# Memory.net
KiCad netlist of a schematic drawn in Altium Designer
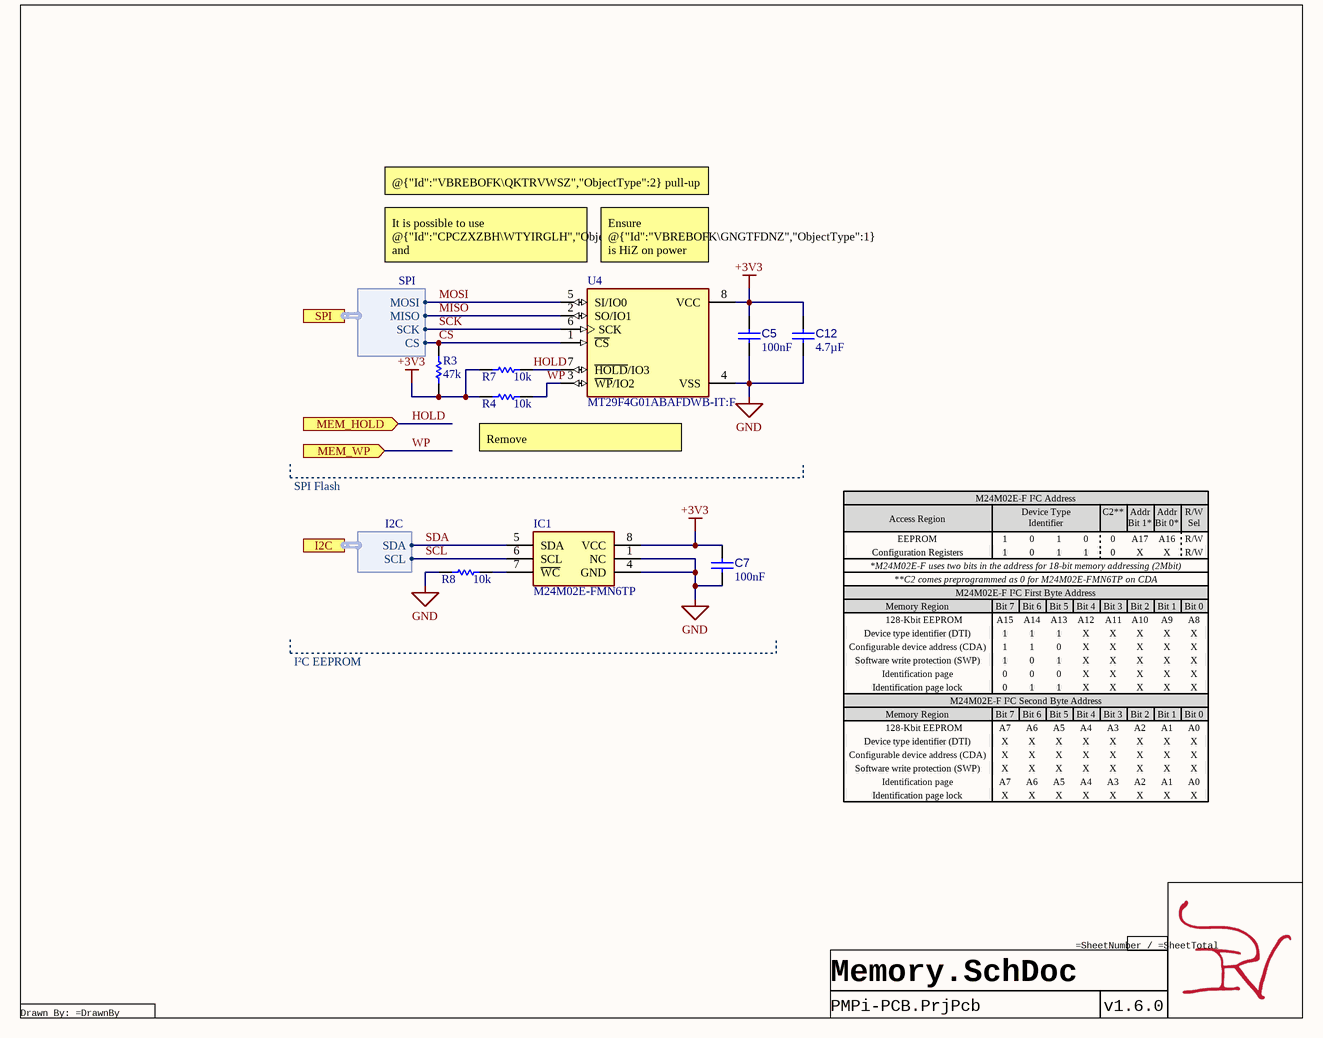
[diagram p0: Memory.SchDoc]

(export (version "E")
  (design (tool "Eeschema 10.0.6"))
  (components
    (comp (ref "C5")
      (value "100nF")
      (footprint "CAP 0402_1005")
      (fields (field (name "TOLERANCE") "10%") (field (name "Comment") "CAP-NP-2"))
      (libsource (lib "IIT Motorsports") (part "CAP-NP-2"))
    )
    (comp (ref "C7")
      (value "100nF")
      (footprint "CAP 0402_1005")
      (fields (field (name "TOLERANCE") "10%") (field (name "Comment") "CAP-NP-2"))
      (libsource (lib "IIT Motorsports") (part "CAP-NP-2"))
    )
    (comp (ref "C12")
      (value "4.7µF")
      (footprint "CAP 0402_1005")
      (fields (field (name "Comment") "CL05A475MP5NRNC"))
      (libsource (lib "IIT Motorsports") (part "CAP-NP-2"))
    )
    (comp (ref "IC1")
      (value "M24M02E-FMN6TP")
      (footprint "SOIC127P600X175-8N")
      (fields (field (name "MOUSER PART NUMBER") "511-M24M02E-FMN6TP"))
      (libsource (lib "IIT Motorsports") (part "M24M02E-FMN6TP"))
    )
    (comp (ref "R3")
      (value "47k")
      (footprint "RES 0402_1005")
      (fields
        (field (name "TOLERANCE") "1%")
        (field (name "POWER") "100mW")
        (field (name "Comment") "47k-0402-0.1/1")
      )
      (libsource (lib "IIT Motorsports") (part "RES"))
    )
    (comp (ref "R4")
      (value "10k")
      (footprint "RES 0402_1005")
      (fields
        (field (name "TOLERANCE") "1%")
        (field (name "POWER") "100mW")
        (field (name "Comment") "10K-0402-0.1/1")
      )
      (libsource (lib "IIT Motorsports") (part "RES"))
    )
    (comp (ref "R7")
      (value "10k")
      (footprint "RES 0402_1005")
      (fields
        (field (name "TOLERANCE") "1%")
        (field (name "POWER") "100mW")
        (field (name "Comment") "10K-0402-0.1/1")
      )
      (libsource (lib "IIT Motorsports") (part "RES"))
    )
    (comp (ref "R8")
      (value "10k")
      (footprint "RES 0402_1005")
      (fields
        (field (name "TOLERANCE") "1%")
        (field (name "POWER") "100mW")
        (field (name "Comment") "10K-0402-0.1/1")
      )
      (libsource (lib "IIT Motorsports") (part "RES"))
    )
    (comp (ref "U4")
      (value "MT29F4G01ABAFDWB-IT:F")
      (footprint "FP-WB-IPC_B")
      (description "SLC NAND Flash Serial-SPI 3.3V 4Gbit 4G X 1bit 5ns/6ns 8-Pin UPDFN Tray")
      (libsource (lib "IIT Motorsports") (part "2a22d8121842150c115fe802c55be1a"))
    )
  )
  (nets
    (net (code "3") (name "+3V3") (class "Default")
      (node (ref "C12") (pin "2") (pinfunction "2_2") (pintype "passive"))
      (node (ref "C5") (pin "2") (pinfunction "2_2") (pintype "passive"))
      (node (ref "C7") (pin "2") (pinfunction "2_2") (pintype "passive"))
      (node (ref "IC1") (pin "8") (pinfunction "VCC_8") (pintype "passive"))
      (node (ref "R3") (pin "1") (pinfunction "1_1") (pintype "passive"))
      (node (ref "R4") (pin "1") (pinfunction "1_1") (pintype "passive"))
      (node (ref "R7") (pin "1") (pinfunction "1_1") (pintype "passive"))
      (node (ref "U4") (pin "8") (pinfunction "VCC_8") (pintype "power_in"))
    )
    (net (code "4") (name "/CS") (class "Default")
      (node (ref "R3") (pin "2") (pinfunction "2_2") (pintype "passive"))
      (node (ref "U4") (pin "1") (pinfunction "~{CS}_1") (pintype "input"))
    )
    (net (code "5") (name "/HOLD") (class "Default")
      (node (ref "R7") (pin "2") (pinfunction "2_2") (pintype "passive"))
      (node (ref "U4") (pin "7") (pinfunction "~{HOLD}/IO3_7") (pintype "bidirectional"))
    )
    (net (code "6") (name "/MISO") (class "Default")
      (node (ref "U4") (pin "2") (pinfunction "SO/IO1_2") (pintype "bidirectional"))
    )
    (net (code "7") (name "/MOSI") (class "Default")
      (node (ref "U4") (pin "5") (pinfunction "SI/IO0_5") (pintype "bidirectional"))
    )
    (net (code "8") (name "/SCK") (class "Default")
      (node (ref "U4") (pin "6") (pinfunction "SCK_6") (pintype "input"))
    )
    (net (code "9") (name "/SCL") (class "Default")
      (node (ref "IC1") (pin "6") (pinfunction "SCL_6") (pintype "passive"))
    )
    (net (code "10") (name "/SDA") (class "Default")
      (node (ref "IC1") (pin "5") (pinfunction "SDA_5") (pintype "passive"))
    )
    (net (code "11") (name "/WP") (class "Default")
      (node (ref "R4") (pin "2") (pinfunction "2_2") (pintype "passive"))
      (node (ref "U4") (pin "3") (pinfunction "~{WP}/IO2_3") (pintype "bidirectional"))
    )
    (net (code "14") (name "GND") (class "Default")
      (node (ref "C12") (pin "1") (pinfunction "1_1") (pintype "passive"))
      (node (ref "C5") (pin "1") (pinfunction "1_1") (pintype "passive"))
      (node (ref "C7") (pin "1") (pinfunction "1_1") (pintype "passive"))
      (node (ref "IC1") (pin "1") (pinfunction "NC_1") (pintype "passive"))
      (node (ref "IC1") (pin "4") (pinfunction "GND_4") (pintype "passive"))
      (node (ref "R8") (pin "1") (pinfunction "1_1") (pintype "passive"))
      (node (ref "U4") (pin "4") (pinfunction "VSS_4") (pintype "power_in"))
    )
    (net (code "15") (name "Net-(IC1-~{WC})") (class "Default")
      (node (ref "IC1") (pin "7") (pinfunction "~{WC}_7") (pintype "passive"))
      (node (ref "R8") (pin "2") (pinfunction "2_2") (pintype "passive"))
    )
  )
)
